# LED_Driver_NE2B757GT.net
KiCad netlist of a schematic drawn in Altium Designer
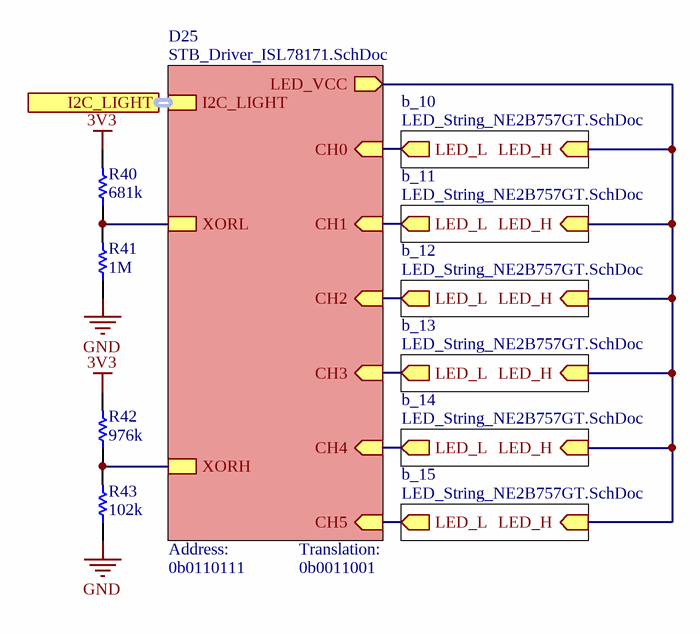
[diagram p0: LED_Driver_NE2B757GT.SchDoc]

(export (version "E")
  (design (tool "Eeschema 10.0.6"))
  (components
    (comp (ref "R40")
      (value "681k")
      (footprint "RESC1005X40X25LL05T05")
      (fields
        (field (name "MANUFACTURER") "Panasonic")
        (field (name "PART NUMBER") "ERJ-2RKF6813X")
        (field (name "TOLERANCE") "1%")
      )
      (libsource (lib "Altium Content Vault") (part "RES"))
    )
    (comp (ref "R41")
      (value "1M")
      (footprint "RESC1005X40X25LL05T05")
      (description "Chip Resistor, 1 MOhm, +/- 1%, 100 mW, -55 to 155 degC, 0402 (1005 Metric), RoHS, Tape and Reel")
      (fields (field (name "PARTNUMBER") "ERJ-2RKF1004X") (field (name "TOLERANCE") "1%"))
      (libsource (lib "Altium Content Vault") (part "RES-2"))
    )
    (comp (ref "R42")
      (value "976k")
      (footprint "RESC1005X40X25LL05T05")
      (fields
        (field (name "MANUFACTURER") "Panasonic")
        (field (name "PART NUMBER") "ERJ-2RKF9763X")
        (field (name "TOLERANCE") "1%")
      )
      (libsource (lib "Altium Content Vault") (part "RES"))
    )
    (comp (ref "R43")
      (value "102k")
      (footprint "RESC1005X40X25LL05T05")
      (fields
        (field (name "MANUFACTURER") "Panasonic")
        (field (name "PART NUMBER") "ERJ-2RKF1023X")
        (field (name "TOLERANCE") "1%")
      )
      (libsource (lib "Altium Content Vault") (part "RES"))
    )
  )
  (nets
    (net (code "10") (name "/XORH") (class "Default")
      (node (ref "R42") (pin "1") (pinfunction "1_1") (pintype "passive"))
      (node (ref "R43") (pin "2") (pinfunction "2_2") (pintype "passive"))
    )
    (net (code "11") (name "/XORL") (class "Default")
      (node (ref "R40") (pin "1") (pinfunction "1_1") (pintype "passive"))
      (node (ref "R41") (pin "2") (pinfunction "2_2") (pintype "passive"))
    )
    (net (code "12") (name "3V3") (class "Default")
      (node (ref "R40") (pin "2") (pinfunction "2_2") (pintype "passive"))
      (node (ref "R42") (pin "2") (pinfunction "2_2") (pintype "passive"))
    )
    (net (code "13") (name "GND") (class "Default")
      (node (ref "R41") (pin "1") (pinfunction "1_1") (pintype "passive"))
      (node (ref "R43") (pin "1") (pinfunction "1_1") (pintype "passive"))
    )
  )
)
